# LDR_V2.net
KiCad netlist of a schematic drawn in EAGLE
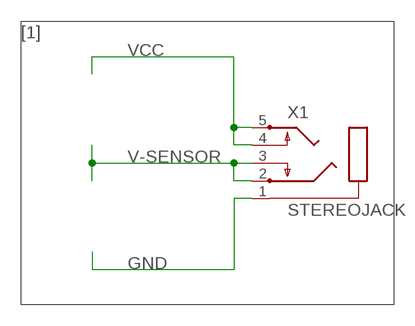
[diagram p0: schematic, sheet 1]
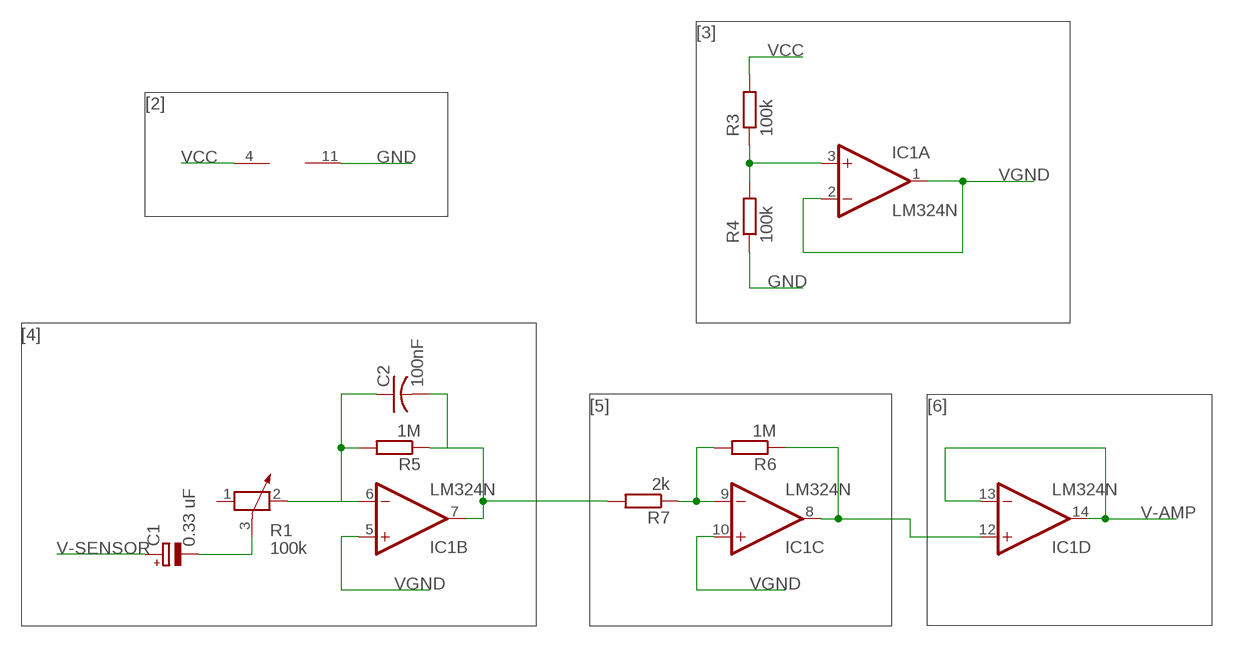
[diagram p1: schematic, sheet 2]
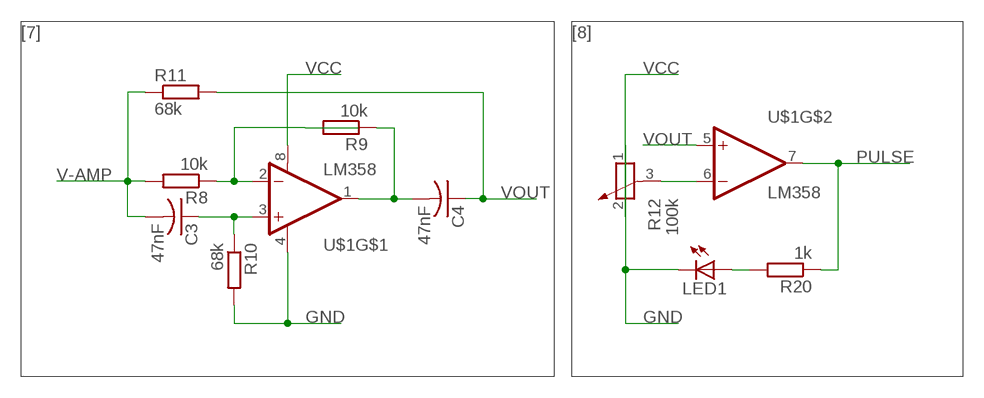
[diagram p2: schematic, sheet 3]
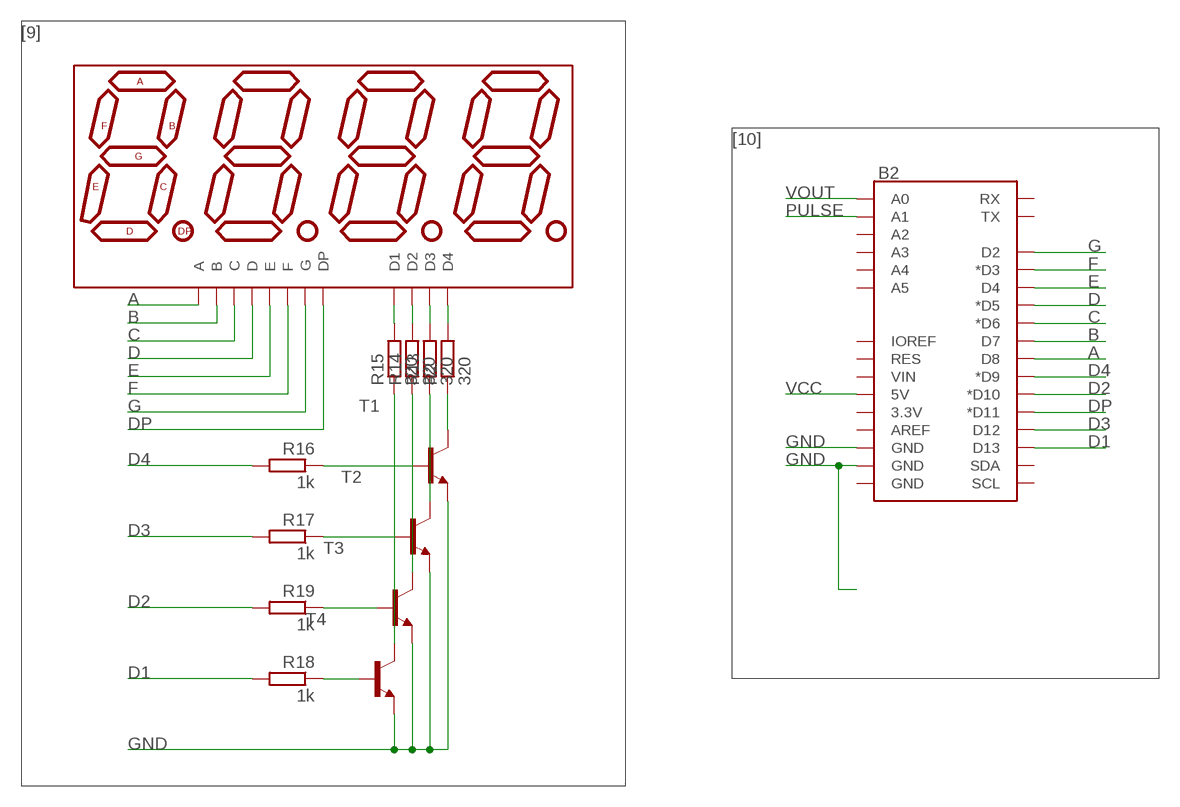
[diagram p3: schematic, sheet 4]

(export (version "E")
  (design (tool "Eeschema 10.0.6"))
  (components
    (comp (ref "C3")
      (value "47nF")
      (footprint "eagle-import:C025-025X050")
      (libsource (lib "eagle-import") (part "C-US025-025X050"))
    )
    (comp (ref "C4")
      (value "47nF")
      (footprint "eagle-import:C025-025X050")
      (libsource (lib "eagle-import") (part "C-US025-025X050"))
    )
    (comp (ref "LED1")
      (value "LED5MM")
      (footprint "eagle-import:LED5MM")
      (libsource (lib "eagle-import") (part "LED5MM"))
    )
    (comp (ref "R8")
      (value "10k")
      (footprint "eagle-import:0207_7")
      (libsource (lib "eagle-import") (part "R-EU_0207/7"))
    )
    (comp (ref "R9")
      (value "10k")
      (footprint "eagle-import:0207_7")
      (libsource (lib "eagle-import") (part "R-EU_0207/7"))
    )
    (comp (ref "R10")
      (value "68k")
      (footprint "eagle-import:0207_7")
      (libsource (lib "eagle-import") (part "R-EU_0207/7"))
    )
    (comp (ref "R11")
      (value "68k")
      (footprint "eagle-import:0207_7")
      (libsource (lib "eagle-import") (part "R-EU_0207/7"))
    )
    (comp (ref "R12")
      (value "100k")
      (footprint "eagle-import:PT-10")
      (libsource (lib "eagle-import") (part "POTENTIOMETER_PT-10"))
    )
    (comp (ref "R20")
      (value "1k")
      (footprint "eagle-import:0207_7")
      (libsource (lib "eagle-import") (part "R-EU_0207/7"))
    )
    (comp (ref "U$1")
      (value "LM358")
      (footprint "eagle-import:DIP08")
      (libsource (lib "eagle-import") (part "LM358"))
    )
    (comp (ref "X1")
      (value "STEREOJACK")
      (footprint "eagle-import:STX3100")
      (libsource (lib "eagle-import") (part "STEREOJACK"))
    )
    (comp (ref "B2")
      (value "ARDUINO_UNO_R3_SHIELDUNO_R3_SHIELD_LOCK")
      (footprint "eagle-import:UNO_R3_SHIELD_LOCK")
      (libsource (lib "eagle-import") (part "ARDUINO_UNO_R3_SHIELDUNO_R3_SHIELD_LOCK"))
    )
    (comp (ref "DISP2")
      (value "ATA8041AB")
      (footprint "eagle-import:7-SEGMENT-4DIGIT-20MM")
      (libsource (lib "eagle-import") (part "7-SEGMENT-4DIGIT-20MM-BLUE"))
    )
    (comp (ref "R2")
      (value "320")
      (footprint "eagle-import:0207_7")
      (libsource (lib "eagle-import") (part "R-EU_0207/7"))
    )
    (comp (ref "R13")
      (value "320")
      (footprint "eagle-import:0207_7")
      (libsource (lib "eagle-import") (part "R-EU_0207/7"))
    )
    (comp (ref "R14")
      (value "320")
      (footprint "eagle-import:0207_7")
      (libsource (lib "eagle-import") (part "R-EU_0207/7"))
    )
    (comp (ref "R15")
      (value "320")
      (footprint "eagle-import:0207_7")
      (libsource (lib "eagle-import") (part "R-EU_0207/7"))
    )
    (comp (ref "R16")
      (value "1k")
      (footprint "eagle-import:0207_7")
      (libsource (lib "eagle-import") (part "R-EU_0207/7"))
    )
    (comp (ref "R17")
      (value "1k")
      (footprint "eagle-import:0207_7")
      (libsource (lib "eagle-import") (part "R-EU_0207/7"))
    )
    (comp (ref "R18")
      (value "1k")
      (footprint "eagle-import:0207_7")
      (libsource (lib "eagle-import") (part "R-EU_0207/7"))
    )
    (comp (ref "R19")
      (value "1k")
      (footprint "eagle-import:0207_7")
      (libsource (lib "eagle-import") (part "R-EU_0207/7"))
    )
    (comp (ref "T1")
      (value "2N2222-NPN-TO92-EBC")
      (footprint "eagle-import:TO92-EBC")
      (libsource (lib "eagle-import") (part "-NPN-TO92-EBC2N2222"))
    )
    (comp (ref "T2")
      (value "2N2222-NPN-TO92-EBC")
      (footprint "eagle-import:TO92-EBC")
      (libsource (lib "eagle-import") (part "-NPN-TO92-EBC2N2222"))
    )
    (comp (ref "T3")
      (value "2N2222-NPN-TO92-EBC")
      (footprint "eagle-import:TO92-EBC")
      (libsource (lib "eagle-import") (part "-NPN-TO92-EBC2N2222"))
    )
    (comp (ref "T4")
      (value "2N2222-NPN-TO92-EBC")
      (footprint "eagle-import:TO92-EBC")
      (libsource (lib "eagle-import") (part "-NPN-TO92-EBC2N2222"))
    )
    (comp (ref "C1")
      (value "0.33 uF")
      (footprint "eagle-import:E1,8-4")
      (libsource (lib "eagle-import") (part "CPOL-EUE1.8-4"))
    )
    (comp (ref "C2")
      (value "100nF")
      (footprint "eagle-import:C025-025X050")
      (libsource (lib "eagle-import") (part "C-US025-025X050"))
    )
    (comp (ref "IC1")
      (value "LM324N")
      (footprint "eagle-import:DIL14")
      (libsource (lib "eagle-import") (part "LM324N"))
    )
    (comp (ref "R1")
      (value "100k")
      (footprint "eagle-import:PT-10")
      (libsource (lib "eagle-import") (part "POTENTIOMETER_PT-10"))
    )
    (comp (ref "R3")
      (value "100k")
      (footprint "eagle-import:0207_7")
      (libsource (lib "eagle-import") (part "R-EU_0207/7"))
    )
    (comp (ref "R4")
      (value "100k")
      (footprint "eagle-import:0207_7")
      (libsource (lib "eagle-import") (part "R-EU_0207/7"))
    )
    (comp (ref "R5")
      (value "1M")
      (footprint "eagle-import:0207_7")
      (libsource (lib "eagle-import") (part "R-EU_0207/7"))
    )
    (comp (ref "R6")
      (value "1M")
      (footprint "eagle-import:0207_7")
      (libsource (lib "eagle-import") (part "R-EU_0207/7"))
    )
    (comp (ref "R7")
      (value "2k")
      (footprint "eagle-import:0207_7")
      (libsource (lib "eagle-import") (part "R-EU_0207/7"))
    )
  )
  (nets
    (net (code "1") (name "A") (class "Default")
      (node (ref "B2") (pin "D8") (pinfunction "D8_D8") (pintype "bidirectional"))
      (node (ref "DISP2") (pin "11") (pinfunction "A_11") (pintype "bidirectional"))
    )
    (net (code "2") (name "B") (class "Default")
      (node (ref "B2") (pin "D7") (pinfunction "D7_D7") (pintype "bidirectional"))
      (node (ref "DISP2") (pin "7") (pinfunction "B_7") (pintype "bidirectional"))
    )
    (net (code "3") (name "C") (class "Default")
      (node (ref "B2") (pin "D6") (pinfunction "*D6_D6") (pintype "bidirectional"))
      (node (ref "DISP2") (pin "4") (pinfunction "C_4") (pintype "bidirectional"))
    )
    (net (code "4") (name "D") (class "Default")
      (node (ref "B2") (pin "D5") (pinfunction "*D5_D5") (pintype "bidirectional"))
      (node (ref "DISP2") (pin "2") (pinfunction "D_2") (pintype "bidirectional"))
    )
    (net (code "5") (name "D1") (class "Default")
      (node (ref "B2") (pin "D13") (pinfunction "D13_D13") (pintype "bidirectional"))
      (node (ref "R18") (pin "2") (pinfunction "2_2") (pintype "passive"))
    )
    (net (code "6") (name "D2") (class "Default")
      (node (ref "B2") (pin "D10") (pinfunction "*D10_D10") (pintype "bidirectional"))
      (node (ref "R19") (pin "2") (pinfunction "2_2") (pintype "passive"))
    )
    (net (code "7") (name "D3") (class "Default")
      (node (ref "B2") (pin "D12") (pinfunction "D12_D12") (pintype "bidirectional"))
      (node (ref "R17") (pin "2") (pinfunction "2_2") (pintype "passive"))
    )
    (net (code "8") (name "D4") (class "Default")
      (node (ref "B2") (pin "D9") (pinfunction "*D9_D9") (pintype "bidirectional"))
      (node (ref "R16") (pin "2") (pinfunction "2_2") (pintype "passive"))
    )
    (net (code "9") (name "DP") (class "Default")
      (node (ref "B2") (pin "D11") (pinfunction "*D11_D11") (pintype "bidirectional"))
      (node (ref "DISP2") (pin "3") (pinfunction "DP_3") (pintype "bidirectional"))
    )
    (net (code "10") (name "E") (class "Default")
      (node (ref "B2") (pin "D4") (pinfunction "D4_D4") (pintype "bidirectional"))
      (node (ref "DISP2") (pin "1") (pinfunction "E_1") (pintype "bidirectional"))
    )
    (net (code "11") (name "F") (class "Default")
      (node (ref "B2") (pin "D3") (pinfunction "*D3_D3") (pintype "bidirectional"))
      (node (ref "DISP2") (pin "10") (pinfunction "F_10") (pintype "bidirectional"))
    )
    (net (code "12") (name "G") (class "Default")
      (node (ref "B2") (pin "D2") (pinfunction "D2_D2") (pintype "bidirectional"))
      (node (ref "DISP2") (pin "5") (pinfunction "G_5") (pintype "bidirectional"))
    )
    (net (code "13") (name "GND") (class "Default")
      (node (ref "B2") (pin "GND@1") (pinfunction "GND_GND@1") (pintype "bidirectional"))
      (node (ref "B2") (pin "GND@2") (pinfunction "GND_GND@2") (pintype "bidirectional"))
      (node (ref "IC1") (pin "11") (pinfunction "V-_11") (pintype "power_in"))
      (node (ref "LED1") (pin "K") (pinfunction "C_K") (pintype "passive"))
      (node (ref "R10") (pin "2") (pinfunction "2_2") (pintype "passive"))
      (node (ref "R12") (pin "1") (pinfunction "1_1") (pintype "passive"))
      (node (ref "R4") (pin "1") (pinfunction "1_1") (pintype "passive"))
      (node (ref "T1") (pin "E") (pinfunction "E_E") (pintype "passive"))
      (node (ref "T2") (pin "E") (pinfunction "E_E") (pintype "passive"))
      (node (ref "T3") (pin "E") (pinfunction "E_E") (pintype "passive"))
      (node (ref "T4") (pin "E") (pinfunction "E_E") (pintype "passive"))
      (node (ref "U$1") (pin "4") (pinfunction "V-_4") (pintype "power_in"))
      (node (ref "X1") (pin "1") (pinfunction "1_1") (pintype "passive"))
    )
    (net (code "14") (name "Net-(C1-Pad-)") (class "Default")
      (node (ref "C1") (pin "-") (pinfunction "-_-") (pintype "passive"))
      (node (ref "R1") (pin "3") (pinfunction "3_3") (pintype "passive"))
    )
    (net (code "15") (name "Net-(DISP2-D1)") (class "Default")
      (node (ref "DISP2") (pin "12") (pinfunction "D1_12") (pintype "bidirectional"))
      (node (ref "R15") (pin "2") (pinfunction "2_2") (pintype "passive"))
    )
    (net (code "16") (name "Net-(DISP2-D2)") (class "Default")
      (node (ref "DISP2") (pin "9") (pinfunction "D2_9") (pintype "bidirectional"))
      (node (ref "R14") (pin "2") (pinfunction "2_2") (pintype "passive"))
    )
    (net (code "17") (name "Net-(DISP2-D3)") (class "Default")
      (node (ref "DISP2") (pin "8") (pinfunction "D3_8") (pintype "bidirectional"))
      (node (ref "R13") (pin "2") (pinfunction "2_2") (pintype "passive"))
    )
    (net (code "18") (name "Net-(DISP2-D4)") (class "Default")
      (node (ref "DISP2") (pin "6") (pinfunction "D4_6") (pintype "bidirectional"))
      (node (ref "R2") (pin "2") (pinfunction "2_2") (pintype "passive"))
    )
    (net (code "19") (name "Net-(IC1A-+IN)") (class "Default")
      (node (ref "IC1") (pin "3") (pinfunction "+IN_3") (pintype "input"))
      (node (ref "R3") (pin "1") (pinfunction "1_1") (pintype "passive"))
      (node (ref "R4") (pin "2") (pinfunction "2_2") (pintype "passive"))
    )
    (net (code "20") (name "Net-(IC1B--IN)") (class "Default")
      (node (ref "C2") (pin "1") (pinfunction "1_1") (pintype "passive"))
      (node (ref "IC1") (pin "6") (pinfunction "-IN_6") (pintype "input"))
      (node (ref "R1") (pin "2") (pinfunction "2_2") (pintype "passive"))
      (node (ref "R5") (pin "2") (pinfunction "2_2") (pintype "passive"))
    )
    (net (code "21") (name "Net-(IC1B-OUT)") (class "Default")
      (node (ref "C2") (pin "2") (pinfunction "2_2") (pintype "passive"))
      (node (ref "IC1") (pin "7") (pinfunction "OUT_7") (pintype "output"))
      (node (ref "R5") (pin "1") (pinfunction "1_1") (pintype "passive"))
      (node (ref "R7") (pin "2") (pinfunction "2_2") (pintype "passive"))
    )
    (net (code "22") (name "Net-(IC1C--IN)") (class "Default")
      (node (ref "IC1") (pin "9") (pinfunction "-IN_9") (pintype "input"))
      (node (ref "R6") (pin "2") (pinfunction "2_2") (pintype "passive"))
      (node (ref "R7") (pin "1") (pinfunction "1_1") (pintype "passive"))
    )
    (net (code "23") (name "Net-(IC1C-OUT)") (class "Default")
      (node (ref "IC1") (pin "12") (pinfunction "+IN_12") (pintype "input"))
      (node (ref "IC1") (pin "8") (pinfunction "OUT_8") (pintype "output"))
      (node (ref "R6") (pin "1") (pinfunction "1_1") (pintype "passive"))
    )
    (net (code "24") (name "Net-(LED1-PadA)") (class "Default")
      (node (ref "LED1") (pin "A") (pinfunction "A_A") (pintype "passive"))
      (node (ref "R20") (pin "2") (pinfunction "2_2") (pintype "passive"))
    )
    (net (code "25") (name "Net-(R2-Pad1)") (class "Default")
      (node (ref "R2") (pin "1") (pinfunction "1_1") (pintype "passive"))
      (node (ref "T1") (pin "C") (pinfunction "C_C") (pintype "passive"))
    )
    (net (code "26") (name "Net-(R13-Pad1)") (class "Default")
      (node (ref "R13") (pin "1") (pinfunction "1_1") (pintype "passive"))
      (node (ref "T2") (pin "C") (pinfunction "C_C") (pintype "passive"))
    )
    (net (code "27") (name "Net-(R14-Pad1)") (class "Default")
      (node (ref "R14") (pin "1") (pinfunction "1_1") (pintype "passive"))
      (node (ref "T3") (pin "C") (pinfunction "C_C") (pintype "passive"))
    )
    (net (code "28") (name "Net-(R15-Pad1)") (class "Default")
      (node (ref "R15") (pin "1") (pinfunction "1_1") (pintype "passive"))
      (node (ref "T4") (pin "C") (pinfunction "C_C") (pintype "passive"))
    )
    (net (code "29") (name "Net-(R16-Pad1)") (class "Default")
      (node (ref "R16") (pin "1") (pinfunction "1_1") (pintype "passive"))
      (node (ref "T1") (pin "B") (pinfunction "B_B") (pintype "passive"))
    )
    (net (code "30") (name "Net-(R17-Pad1)") (class "Default")
      (node (ref "R17") (pin "1") (pinfunction "1_1") (pintype "passive"))
      (node (ref "T2") (pin "B") (pinfunction "B_B") (pintype "passive"))
    )
    (net (code "31") (name "Net-(R18-Pad1)") (class "Default")
      (node (ref "R18") (pin "1") (pinfunction "1_1") (pintype "passive"))
      (node (ref "T4") (pin "B") (pinfunction "B_B") (pintype "passive"))
    )
    (net (code "32") (name "Net-(R19-Pad1)") (class "Default")
      (node (ref "R19") (pin "1") (pinfunction "1_1") (pintype "passive"))
      (node (ref "T3") (pin "B") (pinfunction "B_B") (pintype "passive"))
    )
    (net (code "33") (name "Net-(U$1A-+IN)") (class "Default")
      (node (ref "C3") (pin "1") (pinfunction "1_1") (pintype "passive"))
      (node (ref "R10") (pin "1") (pinfunction "1_1") (pintype "passive"))
      (node (ref "U$1") (pin "3") (pinfunction "+IN_3") (pintype "input"))
    )
    (net (code "34") (name "Net-(U$1A--IN)") (class "Default")
      (node (ref "R8") (pin "1") (pinfunction "1_1") (pintype "passive"))
      (node (ref "R9") (pin "2") (pinfunction "2_2") (pintype "passive"))
      (node (ref "U$1") (pin "2") (pinfunction "-IN_2") (pintype "input"))
    )
    (net (code "35") (name "Net-(U$1A-OUT)") (class "Default")
      (node (ref "C4") (pin "2") (pinfunction "2_2") (pintype "passive"))
      (node (ref "R9") (pin "1") (pinfunction "1_1") (pintype "passive"))
      (node (ref "U$1") (pin "1") (pinfunction "OUT_1") (pintype "output"))
    )
    (net (code "36") (name "Net-(U$1B--IN)") (class "Default")
      (node (ref "R12") (pin "3") (pinfunction "3_3") (pintype "passive"))
      (node (ref "U$1") (pin "6") (pinfunction "-IN_6") (pintype "input"))
    )
    (net (code "37") (name "PULSE") (class "Default")
      (node (ref "B2") (pin "A1") (pinfunction "A1_A1") (pintype "bidirectional"))
      (node (ref "R20") (pin "1") (pinfunction "1_1") (pintype "passive"))
      (node (ref "U$1") (pin "7") (pinfunction "OUT_7") (pintype "output"))
    )
    (net (code "38") (name "V-AMP") (class "Default")
      (node (ref "C3") (pin "2") (pinfunction "2_2") (pintype "passive"))
      (node (ref "IC1") (pin "13") (pinfunction "-IN_13") (pintype "input"))
      (node (ref "IC1") (pin "14") (pinfunction "OUT_14") (pintype "output"))
      (node (ref "R11") (pin "1") (pinfunction "1_1") (pintype "passive"))
      (node (ref "R8") (pin "2") (pinfunction "2_2") (pintype "passive"))
    )
    (net (code "39") (name "V-SENSOR") (class "Default")
      (node (ref "C1") (pin "+") (pinfunction "+_+") (pintype "passive"))
      (node (ref "X1") (pin "2") (pinfunction "2_2") (pintype "passive"))
      (node (ref "X1") (pin "3") (pinfunction "3_3") (pintype "passive"))
    )
    (net (code "40") (name "VCC") (class "Default")
      (node (ref "B2") (pin "5V") (pinfunction "5V_5V") (pintype "bidirectional"))
      (node (ref "IC1") (pin "4") (pinfunction "V+_4") (pintype "power_in"))
      (node (ref "R12") (pin "2") (pinfunction "2_2") (pintype "passive"))
      (node (ref "R3") (pin "2") (pinfunction "2_2") (pintype "passive"))
      (node (ref "U$1") (pin "8") (pinfunction "V+_8") (pintype "power_in"))
      (node (ref "X1") (pin "4") (pinfunction "4_4") (pintype "passive"))
      (node (ref "X1") (pin "5") (pinfunction "5_5") (pintype "passive"))
    )
    (net (code "41") (name "VGND") (class "Default")
      (node (ref "IC1") (pin "1") (pinfunction "OUT_1") (pintype "output"))
      (node (ref "IC1") (pin "10") (pinfunction "+IN_10") (pintype "input"))
      (node (ref "IC1") (pin "2") (pinfunction "-IN_2") (pintype "input"))
      (node (ref "IC1") (pin "5") (pinfunction "+IN_5") (pintype "input"))
    )
    (net (code "42") (name "VOUT") (class "Default")
      (node (ref "B2") (pin "A0") (pinfunction "A0_A0") (pintype "bidirectional"))
      (node (ref "C4") (pin "1") (pinfunction "1_1") (pintype "passive"))
      (node (ref "R11") (pin "2") (pinfunction "2_2") (pintype "passive"))
      (node (ref "U$1") (pin "5") (pinfunction "+IN_5") (pintype "input"))
    )
    (net (code "43") (name "unconnected-(B2-GND-PadGND@0)") (class "Default")
      (node (ref "B2") (pin "GND@0") (pinfunction "GND_GND@0") (pintype "bidirectional"))
    )
    (net (code "44") (name "unconnected-(B2-Pad3.3V)") (class "Default")
      (node (ref "B2") (pin "3.3V") (pinfunction "3.3V_3.3V") (pintype "bidirectional"))
    )
    (net (code "45") (name "unconnected-(B2-PadA2)") (class "Default")
      (node (ref "B2") (pin "A2") (pinfunction "A2_A2") (pintype "bidirectional"))
    )
    (net (code "46") (name "unconnected-(B2-PadA3)") (class "Default")
      (node (ref "B2") (pin "A3") (pinfunction "A3_A3") (pintype "bidirectional"))
    )
    (net (code "47") (name "unconnected-(B2-PadA4)") (class "Default")
      (node (ref "B2") (pin "A4") (pinfunction "A4_A4") (pintype "bidirectional"))
    )
    (net (code "48") (name "unconnected-(B2-PadA5)") (class "Default")
      (node (ref "B2") (pin "A5") (pinfunction "A5_A5") (pintype "bidirectional"))
    )
    (net (code "49") (name "unconnected-(B2-PadAREF)") (class "Default")
      (node (ref "B2") (pin "AREF") (pinfunction "AREF_AREF") (pintype "bidirectional"))
    )
    (net (code "50") (name "unconnected-(B2-PadIOREF)") (class "Default")
      (node (ref "B2") (pin "IOREF") (pinfunction "IOREF_IOREF") (pintype "bidirectional"))
    )
    (net (code "51") (name "unconnected-(B2-PadRES)") (class "Default")
      (node (ref "B2") (pin "RES") (pinfunction "RES_RES") (pintype "bidirectional"))
    )
    (net (code "52") (name "unconnected-(B2-PadRX)") (class "Default")
      (node (ref "B2") (pin "RX") (pinfunction "RX_RX") (pintype "bidirectional"))
    )
    (net (code "53") (name "unconnected-(B2-PadSCL)") (class "Default")
      (node (ref "B2") (pin "SCL") (pinfunction "SCL_SCL") (pintype "bidirectional"))
    )
    (net (code "54") (name "unconnected-(B2-PadSDA)") (class "Default")
      (node (ref "B2") (pin "SDA") (pinfunction "SDA_SDA") (pintype "bidirectional"))
    )
    (net (code "55") (name "unconnected-(B2-PadTX)") (class "Default")
      (node (ref "B2") (pin "TX") (pinfunction "TX_TX") (pintype "bidirectional"))
    )
    (net (code "56") (name "unconnected-(B2-PadVIN)") (class "Default")
      (node (ref "B2") (pin "VIN") (pinfunction "VIN_VIN") (pintype "bidirectional"))
    )
    (net (code "57") (name "unconnected-(R1-Pad1)") (class "Default")
      (node (ref "R1") (pin "1") (pinfunction "1_1") (pintype "passive"))
    )
  )
)
